# F3-Hexa-Brushed-SIDE-USB-JMPR.net
KiCad netlist of a schematic drawn in EAGLE
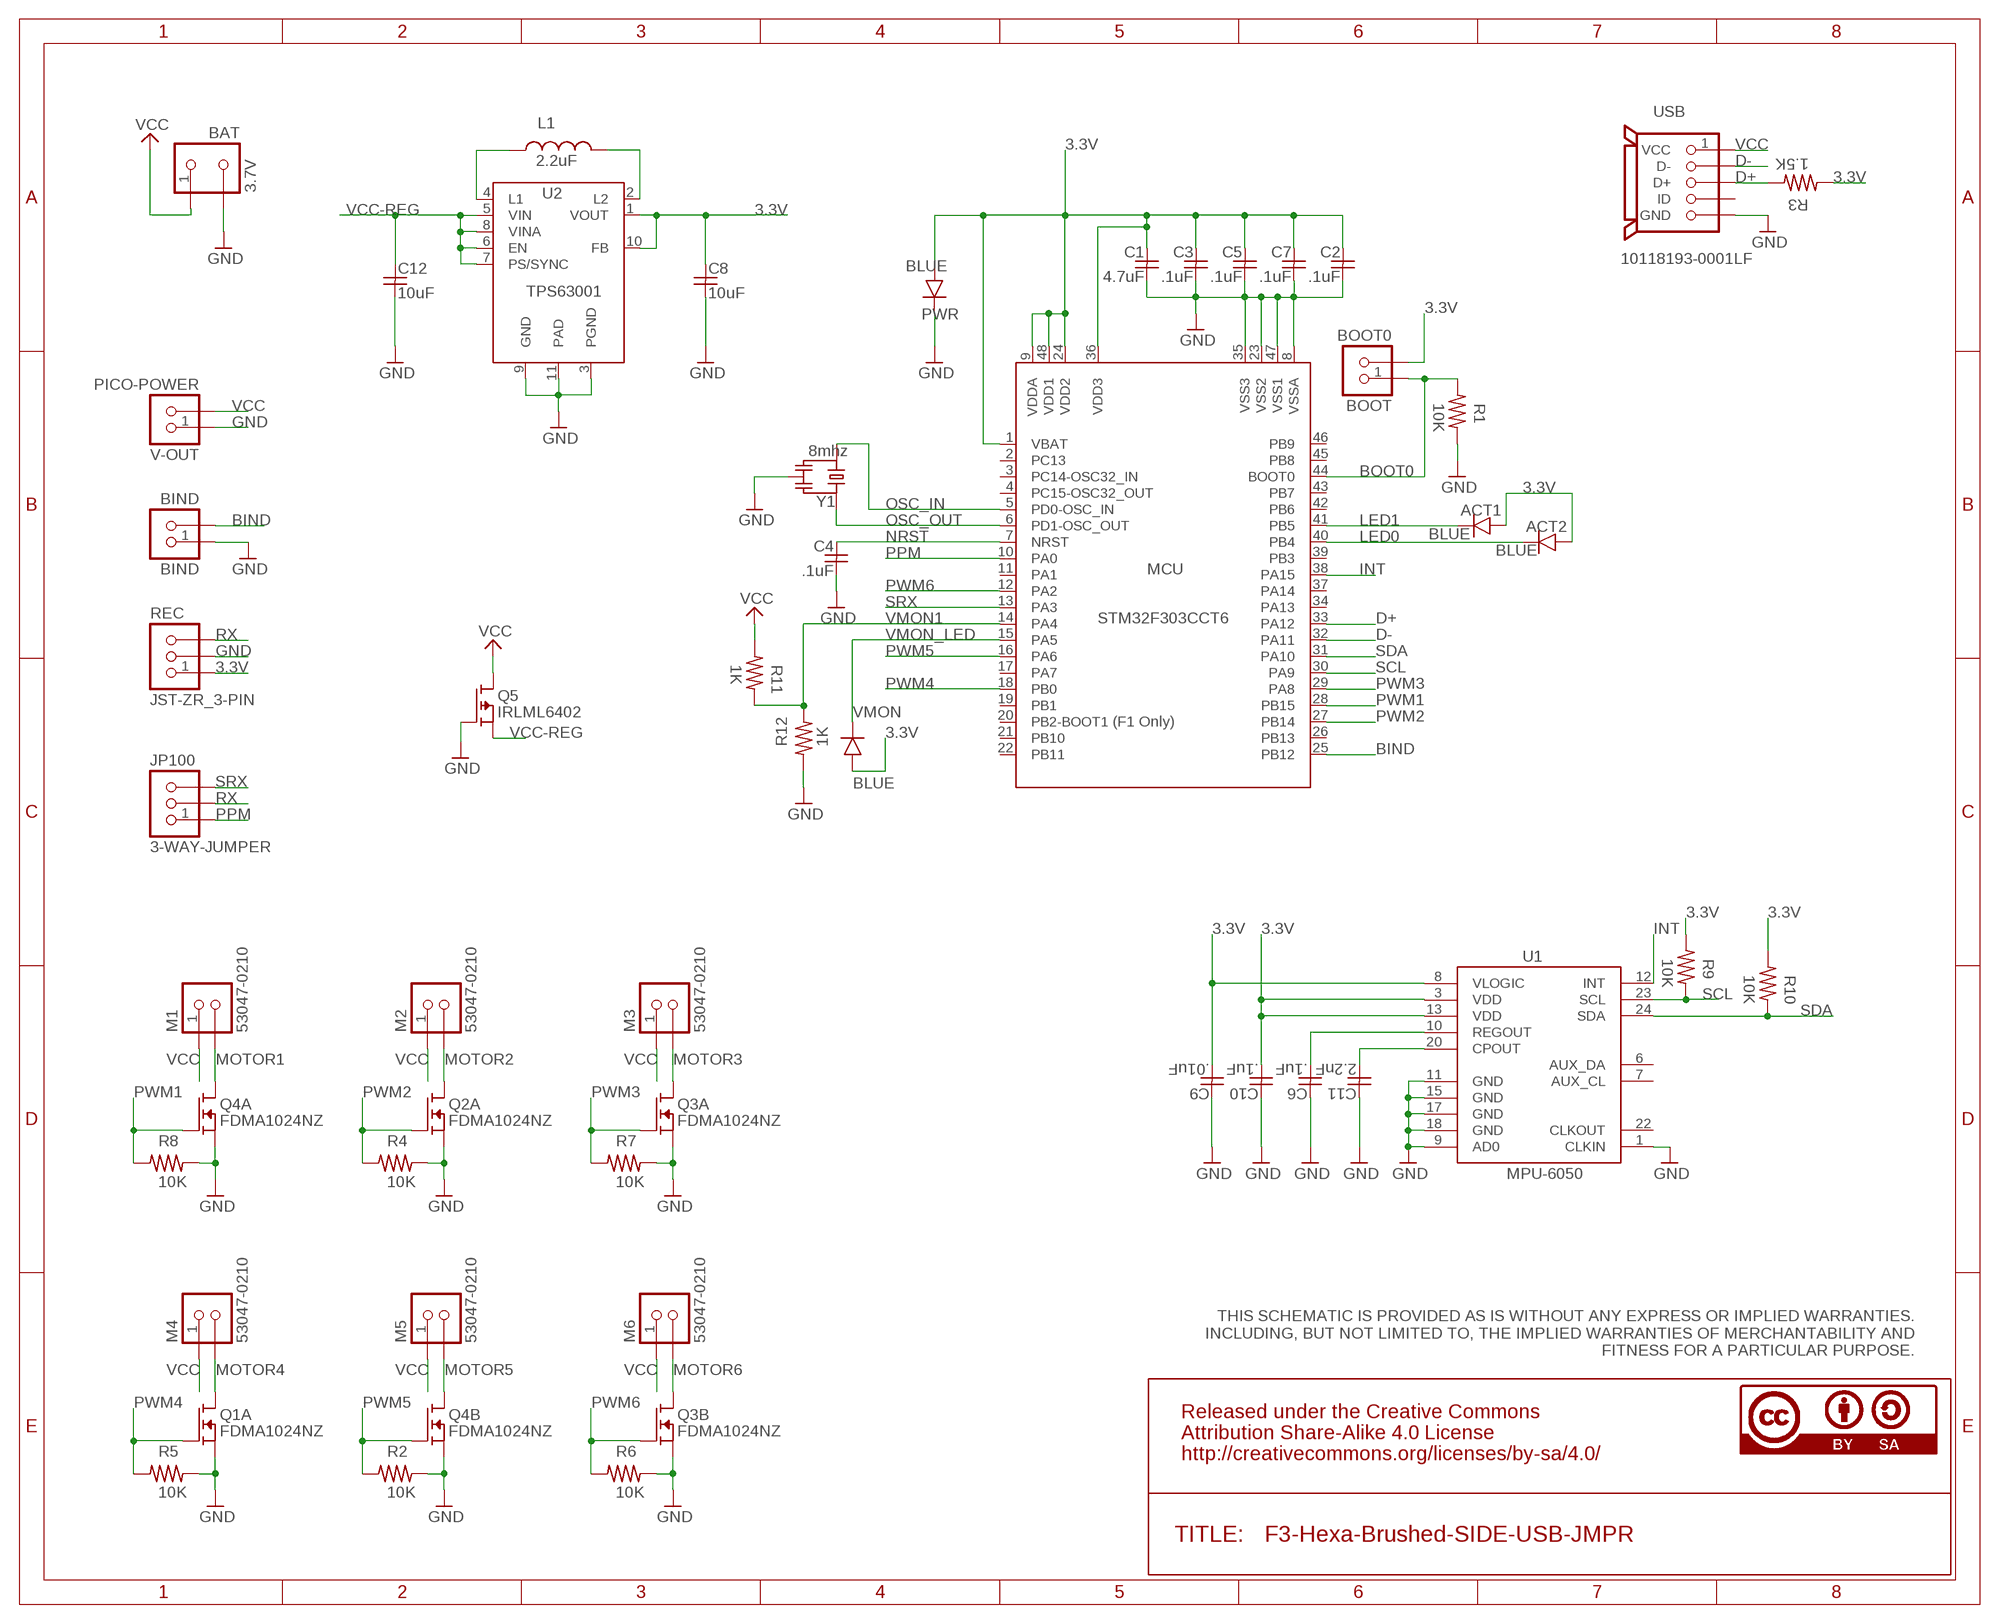
[diagram p0: schematic, sheet 1]

(export (version "E")
  (design (tool "Eeschema 10.0.6"))
  (components
    (comp (ref "ACT1")
      (value "BLUE")
      (footprint "eagle-import:SMD-CHIP-LED-0805")
      (fields (field (name "MF") "Kingbright") (field (name "MPN") "APHCM2012QBC/D-F01"))
      (libsource (lib "eagle-import") (part "SMD-CHIP-LED-0805"))
    )
    (comp (ref "ACT2")
      (value "BLUE")
      (footprint "eagle-import:SMD-CHIP-LED-0805")
      (fields (field (name "MF") "Kingbright") (field (name "MPN") "APHCM2012QBC/D-F01"))
      (libsource (lib "eagle-import") (part "SMD-CHIP-LED-0805"))
    )
    (comp (ref "BAT")
      (value "3.7V")
      (footprint "eagle-import:S2B-PH-K-S")
      (fields (field (name "MF") "JST") (field (name "MPN") "S2B-PH-K-S"))
      (libsource (lib "eagle-import") (part "JST-PH-BAT"))
    )
    (comp (ref "BIND")
      (value "BIND")
      (footprint "eagle-import:1.27MM-PINHEADX2")
      (fields (field (name "MF") "Sullins") (field (name "MPN") "GRPB021VWVN-RC (JUMPER IS M50-1930005)"))
      (libsource (lib "eagle-import") (part "1.27MM-PINHEADX2"))
    )
    (comp (ref "BOOT")
      (value "BOOT0")
      (footprint "eagle-import:1.27MM-PINHEADX2")
      (fields (field (name "MF") "Sullins") (field (name "MPN") "GRPB021VWVN-RC (JUMPER IS M50-1930005)"))
      (libsource (lib "eagle-import") (part "1.27MM-PINHEADX2"))
    )
    (comp (ref "C1")
      (value "4.7uF")
      (footprint "eagle-import:MUR-CAP-0603")
      (fields (field (name "MF") "Murata") (field (name "MPN") "GRJ188C70J475KE11D"))
      (libsource (lib "eagle-import") (part "CAPACITOR4.7UF"))
    )
    (comp (ref "C2")
      (value ".1uF")
      (footprint "eagle-import:MUR-CAP-0603")
      (fields (field (name "MF") "Murata") (field (name "MPN") "GRM188R71C104KA01D"))
      (libsource (lib "eagle-import") (part "CAPACITOR.1UF"))
    )
    (comp (ref "C3")
      (value ".1uF")
      (footprint "eagle-import:MUR-CAP-0603")
      (fields (field (name "MF") "Murata") (field (name "MPN") "GRM188R71C104KA01D"))
      (libsource (lib "eagle-import") (part "CAPACITOR.1UF"))
    )
    (comp (ref "C4")
      (value ".1uF")
      (footprint "eagle-import:MUR-CAP-0603")
      (fields (field (name "MF") "Murata") (field (name "MPN") "GRM188R71C104KA01D"))
      (libsource (lib "eagle-import") (part "CAPACITOR.1UF"))
    )
    (comp (ref "C5")
      (value ".1uF")
      (footprint "eagle-import:MUR-CAP-0603")
      (fields (field (name "MF") "Murata") (field (name "MPN") "GRM188R71C104KA01D"))
      (libsource (lib "eagle-import") (part "CAPACITOR.1UF"))
    )
    (comp (ref "C6")
      (value ".1uF")
      (footprint "eagle-import:MUR-CAP-0603")
      (fields (field (name "MF") "Murata") (field (name "MPN") "GRM188R71C104KA01D"))
      (libsource (lib "eagle-import") (part "CAPACITOR.1UF"))
    )
    (comp (ref "C7")
      (value ".1uF")
      (footprint "eagle-import:MUR-CAP-0603")
      (fields (field (name "MF") "Murata") (field (name "MPN") "GRM188R71C104KA01D"))
      (libsource (lib "eagle-import") (part "CAPACITOR.1UF"))
    )
    (comp (ref "C8")
      (value "10uF")
      (footprint "eagle-import:YUDEN-CAP-0805")
      (fields (field (name "MF") "Taiyo Yuden") (field (name "MPN") "JMK212AB7106KG-T"))
      (libsource (lib "eagle-import") (part "CAPACITOR10UF"))
    )
    (comp (ref "C9")
      (value ".01uF")
      (footprint "eagle-import:MUR-CAP-0603")
      (fields (field (name "MF") "Murata") (field (name "MPN") "GRM188R71C103KA01D"))
      (libsource (lib "eagle-import") (part "CAPACITOR.01UF"))
    )
    (comp (ref "C10")
      (value ".1uF")
      (footprint "eagle-import:MUR-CAP-0603")
      (fields (field (name "MF") "Murata") (field (name "MPN") "GRM188R71C104KA01D"))
      (libsource (lib "eagle-import") (part "CAPACITOR.1UF"))
    )
    (comp (ref "C11")
      (value "2.2nF")
      (footprint "eagle-import:MUR-CAP-0603")
      (fields (field (name "MF") "Murata") (field (name "MPN") "GRM188R71C222KA01D"))
      (libsource (lib "eagle-import") (part "CAPACITOR2.2NF"))
    )
    (comp (ref "C12")
      (value "10uF")
      (footprint "eagle-import:YUDEN-CAP-0805")
      (fields (field (name "MF") "Taiyo Yuden") (field (name "MPN") "JMK212AB7106KG-T"))
      (libsource (lib "eagle-import") (part "CAPACITOR10UF"))
    )
    (comp (ref "JP100")
      (value "3-WAY-JUMPER")
      (footprint "eagle-import:3-WAY-JUMPER")
      (libsource (lib "eagle-import") (part "3-WAY-JUMPER"))
    )
    (comp (ref "L1")
      (value "2.2uF")
      (footprint "eagle-import:NR301X")
      (fields (field (name "MF") "Taiyo Yuden") (field (name "MPN") "NR3015T2R2M"))
      (libsource (lib "eagle-import") (part "NR301X"))
    )
    (comp (ref "M1")
      (value "53047-0210")
      (footprint "eagle-import:PICO-53047-02")
      (fields (field (name "MF") "MOLEX"))
      (libsource (lib "eagle-import") (part "PICO-1.25-MOTOR"))
    )
    (comp (ref "M2")
      (value "53047-0210")
      (footprint "eagle-import:PICO-53047-02")
      (fields (field (name "MF") "MOLEX"))
      (libsource (lib "eagle-import") (part "PICO-1.25-MOTOR"))
    )
    (comp (ref "M3")
      (value "53047-0210")
      (footprint "eagle-import:PICO-53047-02")
      (fields (field (name "MF") "MOLEX"))
      (libsource (lib "eagle-import") (part "PICO-1.25-MOTOR"))
    )
    (comp (ref "M4")
      (value "53047-0210")
      (footprint "eagle-import:PICO-53047-02")
      (fields (field (name "MF") "MOLEX"))
      (libsource (lib "eagle-import") (part "PICO-1.25-MOTOR"))
    )
    (comp (ref "M5")
      (value "53047-0210")
      (footprint "eagle-import:PICO-53047-02")
      (fields (field (name "MF") "MOLEX"))
      (libsource (lib "eagle-import") (part "PICO-1.25-MOTOR"))
    )
    (comp (ref "M6")
      (value "53047-0210")
      (footprint "eagle-import:PICO-53047-02")
      (fields (field (name "MF") "MOLEX"))
      (libsource (lib "eagle-import") (part "PICO-1.25-MOTOR"))
    )
    (comp (ref "MCU")
      (value "STM32F303CCT6")
      (footprint "eagle-import:LQFP48-7X7")
      (fields (field (name "MF") "ST"))
      (libsource (lib "eagle-import") (part "STM32FX03-F3"))
    )
    (comp (ref "PWR")
      (value "BLUE")
      (footprint "eagle-import:SMD-CHIP-LED-0805")
      (fields (field (name "MF") "Kingbright") (field (name "MPN") "APHCM2012QBC/D-F01"))
      (libsource (lib "eagle-import") (part "SMD-CHIP-LED-0805"))
    )
    (comp (ref "Q1")
      (value "FDMA1024NZ")
      (footprint "eagle-import:MICROFET-2X2_DUAL")
      (fields (field (name "MF") "Fairchild"))
      (libsource (lib "eagle-import") (part "FDMA1024NZ"))
    )
    (comp (ref "Q2")
      (value "FDMA1024NZ")
      (footprint "eagle-import:MICROFET-2X2_DUAL")
      (fields (field (name "MF") "Fairchild"))
      (libsource (lib "eagle-import") (part "FDMA1024NZ"))
    )
    (comp (ref "Q3")
      (value "FDMA1024NZ")
      (footprint "eagle-import:MICROFET-2X2_DUAL")
      (fields (field (name "MF") "Fairchild"))
      (libsource (lib "eagle-import") (part "FDMA1024NZ"))
    )
    (comp (ref "Q4")
      (value "FDMA1024NZ")
      (footprint "eagle-import:MICROFET-2X2_DUAL")
      (fields (field (name "MF") "Fairchild"))
      (libsource (lib "eagle-import") (part "FDMA1024NZ"))
    )
    (comp (ref "Q5")
      (value "IRLML6402")
      (footprint "eagle-import:SOT-23")
      (fields (field (name "MF") "IR"))
      (libsource (lib "eagle-import") (part "MOSFET-P"))
    )
    (comp (ref "R1")
      (value "10K")
      (footprint "eagle-import:VISH-RES-0603")
      (fields (field (name "MF") "Vishay") (field (name "MPN") "CRCW060310K0FKEAHP"))
      (libsource (lib "eagle-import") (part "RESISTOR10K"))
    )
    (comp (ref "R2")
      (value "10K")
      (footprint "eagle-import:VISH-RES-0603")
      (fields (field (name "MF") "Vishay") (field (name "MPN") "CRCW060310K0FKEAHP"))
      (libsource (lib "eagle-import") (part "RESISTOR10K"))
    )
    (comp (ref "R3")
      (value "1.5K")
      (footprint "eagle-import:VISH-RES-0603")
      (fields (field (name "MF") "Vishay") (field (name "MPN") "CRCW06031K50FKEAHP"))
      (libsource (lib "eagle-import") (part "RESISTOR1.5K"))
    )
    (comp (ref "R4")
      (value "10K")
      (footprint "eagle-import:VISH-RES-0603")
      (fields (field (name "MF") "Vishay") (field (name "MPN") "CRCW060310K0FKEAHP"))
      (libsource (lib "eagle-import") (part "RESISTOR10K"))
    )
    (comp (ref "R5")
      (value "10K")
      (footprint "eagle-import:VISH-RES-0603")
      (fields (field (name "MF") "Vishay") (field (name "MPN") "CRCW060310K0FKEAHP"))
      (libsource (lib "eagle-import") (part "RESISTOR10K"))
    )
    (comp (ref "R6")
      (value "10K")
      (footprint "eagle-import:VISH-RES-0603")
      (fields (field (name "MF") "Vishay") (field (name "MPN") "CRCW060310K0FKEAHP"))
      (libsource (lib "eagle-import") (part "RESISTOR10K"))
    )
    (comp (ref "R7")
      (value "10K")
      (footprint "eagle-import:VISH-RES-0603")
      (fields (field (name "MF") "Vishay") (field (name "MPN") "CRCW060310K0FKEAHP"))
      (libsource (lib "eagle-import") (part "RESISTOR10K"))
    )
    (comp (ref "R8")
      (value "10K")
      (footprint "eagle-import:VISH-RES-0603")
      (fields (field (name "MF") "Vishay") (field (name "MPN") "CRCW060310K0FKEAHP"))
      (libsource (lib "eagle-import") (part "RESISTOR10K"))
    )
    (comp (ref "R9")
      (value "10K")
      (footprint "eagle-import:VISH-RES-0603")
      (fields (field (name "MF") "Vishay") (field (name "MPN") "CRCW060310K0FKEAHP"))
      (libsource (lib "eagle-import") (part "RESISTOR10K"))
    )
    (comp (ref "R10")
      (value "10K")
      (footprint "eagle-import:VISH-RES-0603")
      (fields (field (name "MF") "Vishay") (field (name "MPN") "CRCW060310K0FKEAHP"))
      (libsource (lib "eagle-import") (part "RESISTOR10K"))
    )
    (comp (ref "R11")
      (value "1K")
      (footprint "eagle-import:VISH-RES-0603")
      (fields (field (name "MF") "Vishay") (field (name "MPN") "CRCW06031K00FKEAHP"))
      (libsource (lib "eagle-import") (part "RESISTOR1K"))
    )
    (comp (ref "R12")
      (value "1K")
      (footprint "eagle-import:VISH-RES-0603")
      (fields (field (name "MF") "Vishay") (field (name "MPN") "CRCW06031K00FKEAHP"))
      (libsource (lib "eagle-import") (part "RESISTOR1K"))
    )
    (comp (ref "REC")
      (value "JST-ZR_3-PIN")
      (footprint "eagle-import:S3B-ZR")
      (fields (field (name "MF") "JST") (field (name "MPN") "S3B-ZR"))
      (libsource (lib "eagle-import") (part "JST-ZR_3-PIN"))
    )
    (comp (ref "U1")
      (value "MPU-6050")
      (footprint "eagle-import:QFN24-4X4")
      (fields (field (name "MF") "Invensense"))
      (libsource (lib "eagle-import") (part "MPU-6050"))
    )
    (comp (ref "U2")
      (value "TPS63001")
      (footprint "eagle-import:VSON-N10")
      (fields (field (name "MF") "TI") (field (name "MPN") "TPS63001DRCR"))
      (libsource (lib "eagle-import") (part "TPS630XX-TPS63001"))
    )
    (comp (ref "USB")
      (value "10118193-0001LF")
      (footprint "eagle-import:10118193-0001LF")
      (fields (field (name "MF") "FCI"))
      (libsource (lib "eagle-import") (part "USB-MICRO-B-FCI"))
    )
    (comp (ref "V-OUT")
      (value "PICO-POWER")
      (footprint "eagle-import:PICO_1.25_.5MM")
      (fields (field (name "MF") "Molex") (field (name "MPN") "53047-0210"))
      (libsource (lib "eagle-import") (part "PICO-POWER"))
    )
    (comp (ref "VMON")
      (value "BLUE")
      (footprint "eagle-import:SMD-CHIP-LED-0805")
      (fields (field (name "MF") "Kingbright") (field (name "MPN") "APHCM2012QBC/D-F01"))
      (libsource (lib "eagle-import") (part "SMD-CHIP-LED-0805"))
    )
    (comp (ref "Y1")
      (value "8mhz")
      (footprint "eagle-import:RESONATOR_8")
      (fields (field (name "MF") "Murata") (field (name "MPN") "CSTCE8M00G55-R0"))
      (libsource (lib "eagle-import") (part "RESONATOR8MHZ"))
    )
  )
  (nets
    (net (code "1") (name "/3.3V") (class "Default")
      (node (ref "ACT1") (pin "A") (pinfunction "A_A") (pintype "passive"))
      (node (ref "ACT2") (pin "A") (pinfunction "A_A") (pintype "passive"))
      (node (ref "BOOT") (pin "2") (pinfunction "2_2") (pintype "passive"))
      (node (ref "C1") (pin "1") (pinfunction "1_1") (pintype "passive"))
      (node (ref "C10") (pin "2") (pinfunction "2_2") (pintype "passive"))
      (node (ref "C2") (pin "1") (pinfunction "1_1") (pintype "passive"))
      (node (ref "C3") (pin "1") (pinfunction "1_1") (pintype "passive"))
      (node (ref "C5") (pin "1") (pinfunction "1_1") (pintype "passive"))
      (node (ref "C7") (pin "1") (pinfunction "1_1") (pintype "passive"))
      (node (ref "C8") (pin "1") (pinfunction "1_1") (pintype "passive"))
      (node (ref "C9") (pin "2") (pinfunction "2_2") (pintype "passive"))
      (node (ref "MCU") (pin "1") (pinfunction "VBAT_1") (pintype "bidirectional"))
      (node (ref "MCU") (pin "24") (pinfunction "VDD2_24") (pintype "bidirectional"))
      (node (ref "MCU") (pin "36") (pinfunction "VDD3_36") (pintype "bidirectional"))
      (node (ref "MCU") (pin "48") (pinfunction "VDD1_48") (pintype "bidirectional"))
      (node (ref "MCU") (pin "9") (pinfunction "VDDA_9") (pintype "bidirectional"))
      (node (ref "PWR") (pin "A") (pinfunction "A_A") (pintype "passive"))
      (node (ref "R10") (pin "2") (pinfunction "2_2") (pintype "passive"))
      (node (ref "R3") (pin "2") (pinfunction "2_2") (pintype "passive"))
      (node (ref "R9") (pin "2") (pinfunction "2_2") (pintype "passive"))
      (node (ref "REC") (pin "1") (pinfunction "1_1") (pintype "bidirectional"))
      (node (ref "U1") (pin "13") (pinfunction "VDD_13") (pintype "bidirectional"))
      (node (ref "U1") (pin "3") (pinfunction "VDD_3") (pintype "bidirectional"))
      (node (ref "U1") (pin "8") (pinfunction "VLOGIC_8") (pintype "bidirectional"))
      (node (ref "U2") (pin "1") (pinfunction "VOUT_1") (pintype "bidirectional"))
      (node (ref "U2") (pin "10") (pinfunction "FB_10") (pintype "bidirectional"))
      (node (ref "VMON") (pin "A") (pinfunction "A_A") (pintype "passive"))
    )
    (net (code "2") (name "/BIND") (class "Default")
      (node (ref "BIND") (pin "2") (pinfunction "2_2") (pintype "passive"))
      (node (ref "MCU") (pin "25") (pinfunction "PB12_25") (pintype "bidirectional"))
    )
    (net (code "3") (name "/BOOT0") (class "Default")
      (node (ref "BOOT") (pin "1") (pinfunction "1_1") (pintype "passive"))
      (node (ref "MCU") (pin "44") (pinfunction "BOOT0_44") (pintype "bidirectional"))
      (node (ref "R1") (pin "2") (pinfunction "2_2") (pintype "passive"))
    )
    (net (code "4") (name "/D+") (class "Default")
      (node (ref "MCU") (pin "33") (pinfunction "PA12_33") (pintype "bidirectional"))
      (node (ref "R3") (pin "1") (pinfunction "1_1") (pintype "passive"))
      (node (ref "USB") (pin "3") (pinfunction "D+_3") (pintype "passive"))
    )
    (net (code "5") (name "/D-") (class "Default")
      (node (ref "MCU") (pin "32") (pinfunction "PA11_32") (pintype "bidirectional"))
      (node (ref "USB") (pin "2") (pinfunction "D-_2") (pintype "passive"))
    )
    (net (code "6") (name "/INT") (class "Default")
      (node (ref "MCU") (pin "38") (pinfunction "PA15_38") (pintype "bidirectional"))
      (node (ref "U1") (pin "12") (pinfunction "INT_12") (pintype "bidirectional"))
    )
    (net (code "7") (name "/LED0") (class "Default")
      (node (ref "ACT2") (pin "C") (pinfunction "C_C") (pintype "passive"))
      (node (ref "MCU") (pin "40") (pinfunction "PB4_40") (pintype "bidirectional"))
    )
    (net (code "8") (name "/LED1") (class "Default")
      (node (ref "ACT1") (pin "C") (pinfunction "C_C") (pintype "passive"))
      (node (ref "MCU") (pin "41") (pinfunction "PB5_41") (pintype "bidirectional"))
    )
    (net (code "9") (name "/MOTOR1") (class "Default")
      (node (ref "M1") (pin "2") (pinfunction "2_2") (pintype "passive"))
      (node (ref "Q4") (pin "A.D") (pinfunction "D_A.D") (pintype "bidirectional"))
      (node (ref "Q4") (pin "A.D1") (pinfunction "D_A.D1") (pintype "bidirectional"))
    )
    (net (code "10") (name "/MOTOR2") (class "Default")
      (node (ref "M2") (pin "2") (pinfunction "2_2") (pintype "passive"))
      (node (ref "Q2") (pin "A.D") (pinfunction "D_A.D") (pintype "bidirectional"))
      (node (ref "Q2") (pin "A.D1") (pinfunction "D_A.D1") (pintype "bidirectional"))
    )
    (net (code "11") (name "/MOTOR3") (class "Default")
      (node (ref "M3") (pin "2") (pinfunction "2_2") (pintype "passive"))
      (node (ref "Q3") (pin "A.D") (pinfunction "D_A.D") (pintype "bidirectional"))
      (node (ref "Q3") (pin "A.D1") (pinfunction "D_A.D1") (pintype "bidirectional"))
    )
    (net (code "12") (name "/MOTOR4") (class "Default")
      (node (ref "M4") (pin "2") (pinfunction "2_2") (pintype "passive"))
      (node (ref "Q1") (pin "A.D") (pinfunction "D_A.D") (pintype "bidirectional"))
      (node (ref "Q1") (pin "A.D1") (pinfunction "D_A.D1") (pintype "bidirectional"))
    )
    (net (code "13") (name "/MOTOR5") (class "Default")
      (node (ref "M5") (pin "2") (pinfunction "2_2") (pintype "passive"))
      (node (ref "Q4") (pin "B.D") (pinfunction "D_B.D") (pintype "bidirectional"))
      (node (ref "Q4") (pin "B.D1") (pinfunction "D_B.D1") (pintype "bidirectional"))
    )
    (net (code "14") (name "/MOTOR6") (class "Default")
      (node (ref "M6") (pin "2") (pinfunction "2_2") (pintype "passive"))
      (node (ref "Q3") (pin "B.D") (pinfunction "D_B.D") (pintype "bidirectional"))
      (node (ref "Q3") (pin "B.D1") (pinfunction "D_B.D1") (pintype "bidirectional"))
    )
    (net (code "15") (name "/NRST") (class "Default")
      (node (ref "C4") (pin "1") (pinfunction "1_1") (pintype "passive"))
      (node (ref "MCU") (pin "7") (pinfunction "NRST_7") (pintype "bidirectional"))
    )
    (net (code "16") (name "/OSC_IN") (class "Default")
      (node (ref "MCU") (pin "5") (pinfunction "PD0-OSC_IN_5") (pintype "bidirectional"))
      (node (ref "Y1") (pin "3") (pinfunction "3_3") (pintype "passive"))
    )
    (net (code "17") (name "/OSC_OUT") (class "Default")
      (node (ref "MCU") (pin "6") (pinfunction "PD1-OSC_OUT_6") (pintype "bidirectional"))
      (node (ref "Y1") (pin "1") (pinfunction "1_1") (pintype "passive"))
    )
    (net (code "18") (name "/PPM") (class "Default")
      (node (ref "JP100") (pin "1") (pinfunction "1_1") (pintype "bidirectional"))
      (node (ref "MCU") (pin "10") (pinfunction "PA0_10") (pintype "bidirectional"))
    )
    (net (code "19") (name "/PWM1") (class "Default")
      (node (ref "MCU") (pin "28") (pinfunction "PB15_28") (pintype "bidirectional"))
      (node (ref "Q4") (pin "A.G") (pinfunction "G_A.G") (pintype "bidirectional"))
      (node (ref "R8") (pin "2") (pinfunction "2_2") (pintype "passive"))
    )
    (net (code "20") (name "/PWM2") (class "Default")
      (node (ref "MCU") (pin "27") (pinfunction "PB14_27") (pintype "bidirectional"))
      (node (ref "Q2") (pin "A.G") (pinfunction "G_A.G") (pintype "bidirectional"))
      (node (ref "R4") (pin "2") (pinfunction "2_2") (pintype "passive"))
    )
    (net (code "21") (name "/PWM3") (class "Default")
      (node (ref "MCU") (pin "29") (pinfunction "PA8_29") (pintype "bidirectional"))
      (node (ref "Q3") (pin "A.G") (pinfunction "G_A.G") (pintype "bidirectional"))
      (node (ref "R7") (pin "2") (pinfunction "2_2") (pintype "passive"))
    )
    (net (code "22") (name "/PWM4") (class "Default")
      (node (ref "MCU") (pin "18") (pinfunction "PB0_18") (pintype "bidirectional"))
      (node (ref "Q1") (pin "A.G") (pinfunction "G_A.G") (pintype "bidirectional"))
      (node (ref "R5") (pin "2") (pinfunction "2_2") (pintype "passive"))
    )
    (net (code "23") (name "/PWM5") (class "Default")
      (node (ref "MCU") (pin "16") (pinfunction "PA6_16") (pintype "bidirectional"))
      (node (ref "Q4") (pin "B.G") (pinfunction "G_B.G") (pintype "bidirectional"))
      (node (ref "R2") (pin "2") (pinfunction "2_2") (pintype "passive"))
    )
    (net (code "24") (name "/PWM6") (class "Default")
      (node (ref "MCU") (pin "12") (pinfunction "PA2_12") (pintype "bidirectional"))
      (node (ref "Q3") (pin "B.G") (pinfunction "G_B.G") (pintype "bidirectional"))
      (node (ref "R6") (pin "2") (pinfunction "2_2") (pintype "passive"))
    )
    (net (code "25") (name "/RX") (class "Default")
      (node (ref "JP100") (pin "2") (pinfunction "2_2") (pintype "bidirectional"))
      (node (ref "REC") (pin "3") (pinfunction "3_3") (pintype "bidirectional"))
    )
    (net (code "26") (name "/SCL") (class "Default")
      (node (ref "MCU") (pin "30") (pinfunction "PA9_30") (pintype "bidirectional"))
      (node (ref "R9") (pin "1") (pinfunction "1_1") (pintype "passive"))
      (node (ref "U1") (pin "23") (pinfunction "SCL_23") (pintype "bidirectional"))
    )
    (net (code "27") (name "/SDA") (class "Default")
      (node (ref "MCU") (pin "31") (pinfunction "PA10_31") (pintype "bidirectional"))
      (node (ref "R10") (pin "1") (pinfunction "1_1") (pintype "passive"))
      (node (ref "U1") (pin "24") (pinfunction "SDA_24") (pintype "bidirectional"))
    )
    (net (code "28") (name "/SRX") (class "Default")
      (node (ref "JP100") (pin "3") (pinfunction "3_3") (pintype "bidirectional"))
      (node (ref "MCU") (pin "13") (pinfunction "PA3_13") (pintype "bidirectional"))
    )
    (net (code "29") (name "/VCC-REG") (class "Default")
      (node (ref "C12") (pin "1") (pinfunction "1_1") (pintype "passive"))
      (node (ref "Q5") (pin "2") (pinfunction "S_2") (pintype "bidirectional"))
      (node (ref "U2") (pin "5") (pinfunction "VIN_5") (pintype "bidirectional"))
      (node (ref "U2") (pin "6") (pinfunction "EN_6") (pintype "bidirectional"))
      (node (ref "U2") (pin "7") (pinfunction "PS/SYNC_7") (pintype "bidirectional"))
      (node (ref "U2") (pin "8") (pinfunction "VINA_8") (pintype "bidirectional"))
    )
    (net (code "30") (name "/VMON1") (class "Default")
      (node (ref "MCU") (pin "14") (pinfunction "PA4_14") (pintype "bidirectional"))
      (node (ref "R11") (pin "1") (pinfunction "1_1") (pintype "passive"))
      (node (ref "R12") (pin "1") (pinfunction "1_1") (pintype "passive"))
    )
    (net (code "31") (name "/VMON_LED") (class "Default")
      (node (ref "MCU") (pin "15") (pinfunction "PA5_15") (pintype "bidirectional"))
      (node (ref "VMON") (pin "C") (pinfunction "C_C") (pintype "passive"))
    )
    (net (code "32") (name "GND") (class "Default")
      (node (ref "BAT") (pin "2") (pinfunction "2_2") (pintype "bidirectional"))
      (node (ref "BIND") (pin "1") (pinfunction "1_1") (pintype "passive"))
      (node (ref "C1") (pin "2") (pinfunction "2_2") (pintype "passive"))
      (node (ref "C10") (pin "1") (pinfunction "1_1") (pintype "passive"))
      (node (ref "C11") (pin "1") (pinfunction "1_1") (pintype "passive"))
      (node (ref "C12") (pin "2") (pinfunction "2_2") (pintype "passive"))
      (node (ref "C2") (pin "2") (pinfunction "2_2") (pintype "passive"))
      (node (ref "C3") (pin "2") (pinfunction "2_2") (pintype "passive"))
      (node (ref "C4") (pin "2") (pinfunction "2_2") (pintype "passive"))
      (node (ref "C5") (pin "2") (pinfunction "2_2") (pintype "passive"))
      (node (ref "C6") (pin "1") (pinfunction "1_1") (pintype "passive"))
      (node (ref "C7") (pin "2") (pinfunction "2_2") (pintype "passive"))
      (node (ref "C8") (pin "2") (pinfunction "2_2") (pintype "passive"))
      (node (ref "C9") (pin "1") (pinfunction "1_1") (pintype "passive"))
      (node (ref "MCU") (pin "23") (pinfunction "VSS2_23") (pintype "bidirectional"))
      (node (ref "MCU") (pin "35") (pinfunction "VSS3_35") (pintype "bidirectional"))
      (node (ref "MCU") (pin "47") (pinfunction "VSS1_47") (pintype "bidirectional"))
      (node (ref "MCU") (pin "8") (pinfunction "VSSA_8") (pintype "bidirectional"))
      (node (ref "PWR") (pin "C") (pinfunction "C_C") (pintype "passive"))
      (node (ref "Q1") (pin "A.S") (pinfunction "S_A.S") (pintype "bidirectional"))
      (node (ref "Q2") (pin "A.S") (pinfunction "S_A.S") (pintype "bidirectional"))
      (node (ref "Q3") (pin "A.S") (pinfunction "S_A.S") (pintype "bidirectional"))
      (node (ref "Q3") (pin "B.S") (pinfunction "S_B.S") (pintype "bidirectional"))
      (node (ref "Q4") (pin "A.S") (pinfunction "S_A.S") (pintype "bidirectional"))
      (node (ref "Q4") (pin "B.S") (pinfunction "S_B.S") (pintype "bidirectional"))
      (node (ref "Q5") (pin "1") (pinfunction "G_1") (pintype "bidirectional"))
      (node (ref "R1") (pin "1") (pinfunction "1_1") (pintype "passive"))
      (node (ref "R12") (pin "2") (pinfunction "2_2") (pintype "passive"))
      (node (ref "R2") (pin "1") (pinfunction "1_1") (pintype "passive"))
      (node (ref "R4") (pin "1") (pinfunction "1_1") (pintype "passive"))
      (node (ref "R5") (pin "1") (pinfunction "1_1") (pintype "passive"))
      (node (ref "R6") (pin "1") (pinfunction "1_1") (pintype "passive"))
      (node (ref "R7") (pin "1") (pinfunction "1_1") (pintype "passive"))
      (node (ref "R8") (pin "1") (pinfunction "1_1") (pintype "passive"))
      (node (ref "REC") (pin "2") (pinfunction "2_2") (pintype "bidirectional"))
      (node (ref "U1") (pin "1") (pinfunction "CLKIN_1") (pintype "bidirectional"))
      (node (ref "U1") (pin "11") (pinfunction "GND_11") (pintype "bidirectional"))
      (node (ref "U1") (pin "15") (pinfunction "GND_15") (pintype "bidirectional"))
      (node (ref "U1") (pin "17") (pinfunction "GND_17") (pintype "bidirectional"))
      (node (ref "U1") (pin "18") (pinfunction "GND_18") (pintype "bidirectional"))
      (node (ref "U1") (pin "9") (pinfunction "AD0_9") (pintype "bidirectional"))
      (node (ref "U2") (pin "11") (pinfunction "PAD_11") (pintype "bidirectional"))
      (node (ref "U2") (pin "3") (pinfunction "PGND_3") (pintype "bidirectional"))
      (node (ref "U2") (pin "9") (pinfunction "GND_9") (pintype "bidirectional"))
      (node (ref "USB") (pin "5") (pinfunction "GND_5") (pintype "passive"))
      (node (ref "USB") (pin "GND") (pinfunction "GND_GND") (pintype "passive"))
      (node (ref "USB") (pin "GND2") (pinfunction "GND_GND2") (pintype "passive"))
      (node (ref "USB") (pin "HOLE1") (pinfunction "GND_HOLE1") (pintype "passive"))
      (node (ref "USB") (pin "HOLE2") (pinfunction "GND_HOLE2") (pintype "passive"))
      (node (ref "V-OUT") (pin "1") (pinfunction "1_1") (pintype "passive"))
      (node (ref "Y1") (pin "2") (pinfunction "2_2") (pintype "passive"))
    )
    (net (code "33") (name "Net-(U1-CPOUT)") (class "Default")
      (node (ref "C11") (pin "2") (pinfunction "2_2") (pintype "passive"))
      (node (ref "U1") (pin "20") (pinfunction "CPOUT_20") (pintype "bidirectional"))
    )
    (net (code "34") (name "Net-(U1-REGOUT)") (class "Default")
      (node (ref "C6") (pin "2") (pinfunction "2_2") (pintype "passive"))
      (node (ref "U1") (pin "10") (pinfunction "REGOUT_10") (pintype "bidirectional"))
    )
    (net (code "35") (name "Net-(U2-L1)") (class "Default")
      (node (ref "L1") (pin "1") (pinfunction "1_1") (pintype "passive"))
      (node (ref "U2") (pin "4") (pinfunction "L1_4") (pintype "bidirectional"))
    )
    (net (code "36") (name "Net-(U2-L2)") (class "Default")
      (node (ref "L1") (pin "2") (pinfunction "2_2") (pintype "passive"))
      (node (ref "U2") (pin "2") (pinfunction "L2_2") (pintype "bidirectional"))
    )
    (net (code "37") (name "VCC") (class "Default")
      (node (ref "BAT") (pin "1") (pinfunction "1_1") (pintype "bidirectional"))
      (node (ref "M1") (pin "1") (pinfunction "1_1") (pintype "passive"))
      (node (ref "M2") (pin "1") (pinfunction "1_1") (pintype "passive"))
      (node (ref "M3") (pin "1") (pinfunction "1_1") (pintype "passive"))
      (node (ref "M4") (pin "1") (pinfunction "1_1") (pintype "passive"))
      (node (ref "M5") (pin "1") (pinfunction "1_1") (pintype "passive"))
      (node (ref "M6") (pin "1") (pinfunction "1_1") (pintype "passive"))
      (node (ref "Q5") (pin "3") (pinfunction "D_3") (pintype "bidirectional"))
      (node (ref "R11") (pin "2") (pinfunction "2_2") (pintype "passive"))
      (node (ref "USB") (pin "1") (pinfunction "VCC_1") (pintype "passive"))
      (node (ref "V-OUT") (pin "2") (pinfunction "2_2") (pintype "passive"))
    )
    (net (code "38") (name "unconnected-(MCU-PA1-Pad11)") (class "Default")
      (node (ref "MCU") (pin "11") (pinfunction "PA1_11") (pintype "bidirectional"))
    )
    (net (code "39") (name "unconnected-(MCU-PA7-Pad17)") (class "Default")
      (node (ref "MCU") (pin "17") (pinfunction "PA7_17") (pintype "bidirectional"))
    )
    (net (code "40") (name "unconnected-(MCU-PA13-Pad34)") (class "Default")
      (node (ref "MCU") (pin "34") (pinfunction "PA13_34") (pintype "bidirectional"))
    )
    (net (code "41") (name "unconnected-(MCU-PA14-Pad37)") (class "Default")
      (node (ref "MCU") (pin "37") (pinfunction "PA14_37") (pintype "bidirectional"))
    )
    (net (code "42") (name "unconnected-(MCU-PB1-Pad19)") (class "Default")
      (node (ref "MCU") (pin "19") (pinfunction "PB1_19") (pintype "bidirectional"))
    )
    (net (code "43") (name "unconnected-(MCU-PB2-BOOT1-Pad20)") (class "Default")
      (node (ref "MCU") (pin "20") (pinfunction "PB2-BOOT1_20") (pintype "bidirectional"))
    )
    (net (code "44") (name "unconnected-(MCU-PB3-Pad39)") (class "Default")
      (node (ref "MCU") (pin "39") (pinfunction "PB3_39") (pintype "bidirectional"))
    )
    (net (code "45") (name "unconnected-(MCU-PB6-Pad42)") (class "Default")
      (node (ref "MCU") (pin "42") (pinfunction "PB6_42") (pintype "bidirectional"))
    )
    (net (code "46") (name "unconnected-(MCU-PB7-Pad43)") (class "Default")
      (node (ref "MCU") (pin "43") (pinfunction "PB7_43") (pintype "bidirectional"))
    )
    (net (code "47") (name "unconnected-(MCU-PB8-Pad45)") (class "Default")
      (node (ref "MCU") (pin "45") (pinfunction "PB8_45") (pintype "bidirectional"))
    )
    (net (code "48") (name "unconnected-(MCU-PB9-Pad46)") (class "Default")
      (node (ref "MCU") (pin "46") (pinfunction "PB9_46") (pintype "bidirectional"))
    )
    (net (code "49") (name "unconnected-(MCU-PB10-Pad21)") (class "Default")
      (node (ref "MCU") (pin "21") (pinfunction "PB10_21") (pintype "bidirectional"))
    )
    (net (code "50") (name "unconnected-(MCU-PB11-Pad22)") (class "Default")
      (node (ref "MCU") (pin "22") (pinfunction "PB11_22") (pintype "bidirectional"))
    )
    (net (code "51") (name "unconnected-(MCU-PB13-Pad26)") (class "Default")
      (node (ref "MCU") (pin "26") (pinfunction "PB13_26") (pintype "bidirectional"))
    )
    (net (code "52") (name "unconnected-(MCU-PC13-Pad2)") (class "Default")
      (node (ref "MCU") (pin "2") (pinfunction "PC13_2") (pintype "bidirectional"))
    )
    (net (code "53") (name "unconnected-(MCU-PC14-OSC32_IN-Pad3)") (class "Default")
      (node (ref "MCU") (pin "3") (pinfunction "PC14-OSC32_IN_3") (pintype "bidirectional"))
    )
    (net (code "54") (name "unconnected-(MCU-PC15-OSC32_OUT-Pad4)") (class "Default")
      (node (ref "MCU") (pin "4") (pinfunction "PC15-OSC32_OUT_4") (pintype "bidirectional"))
    )
    (net (code "55") (name "unconnected-(U1-AUX_CL-Pad7)") (class "Default")
      (node (ref "U1") (pin "7") (pinfunction "AUX_CL_7") (pintype "bidirectional"))
    )
    (net (code "56") (name "unconnected-(U1-AUX_DA-Pad6)") (class "Default")
      (node (ref "U1") (pin "6") (pinfunction "AUX_DA_6") (pintype "bidirectional"))
    )
    (net (code "57") (name "unconnected-(U1-CLKOUT-Pad22)") (class "Default")
      (node (ref "U1") (pin "22") (pinfunction "CLKOUT_22") (pintype "bidirectional"))
    )
    (net (code "58") (name "unconnected-(USB-ID-Pad4)") (class "Default")
      (node (ref "USB") (pin "4") (pinfunction "ID_4") (pintype "passive"))
    )
  )
)
